# PrimeTime.net
KiCad netlist of a schematic drawn in EAGLE
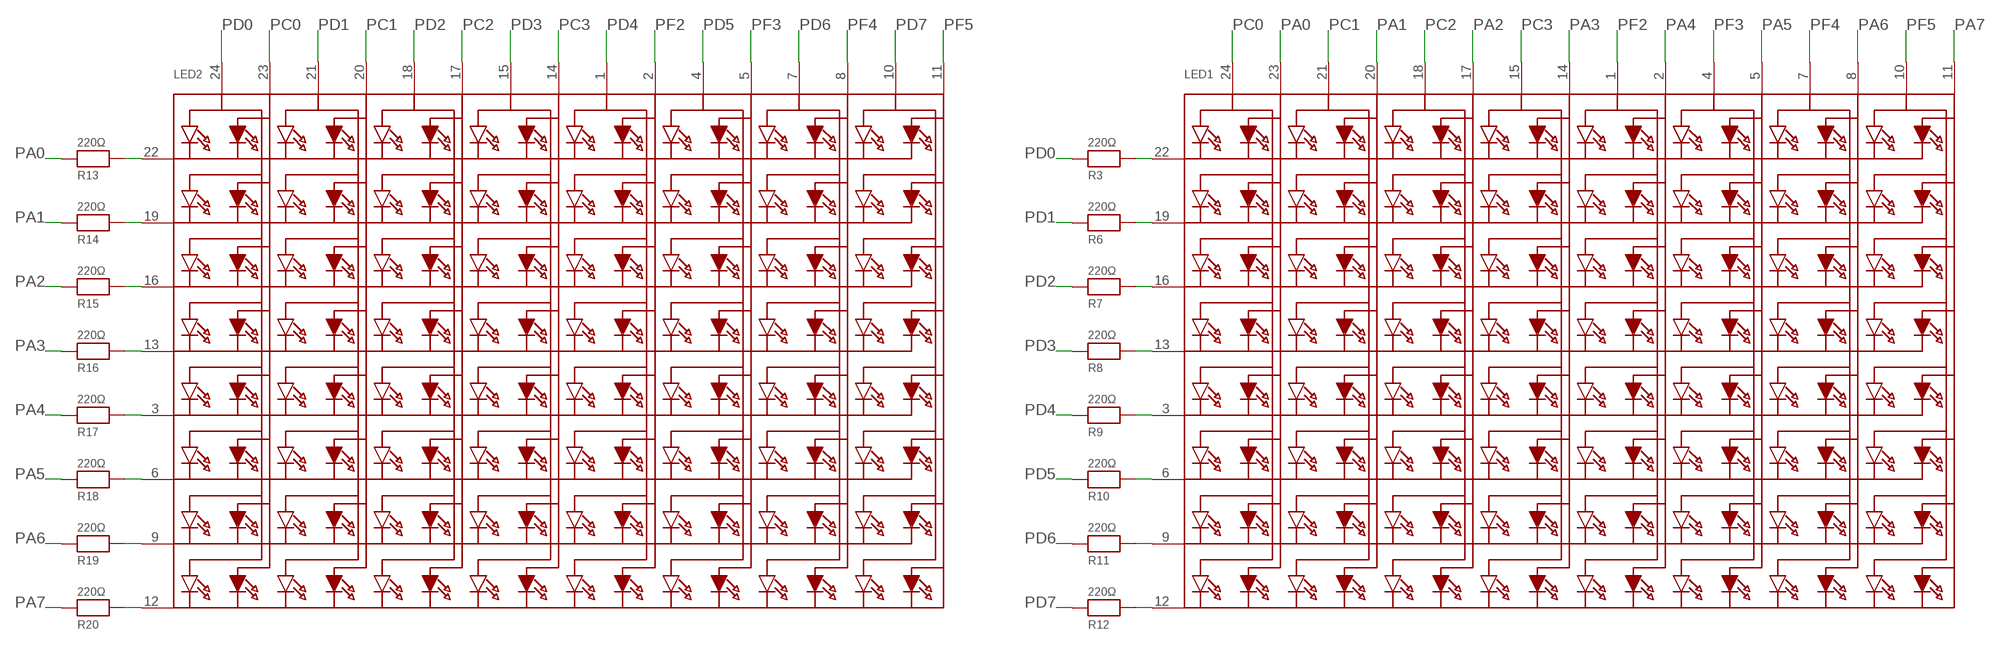
[diagram p0: schematic, sheet 1, part 1 of 2]
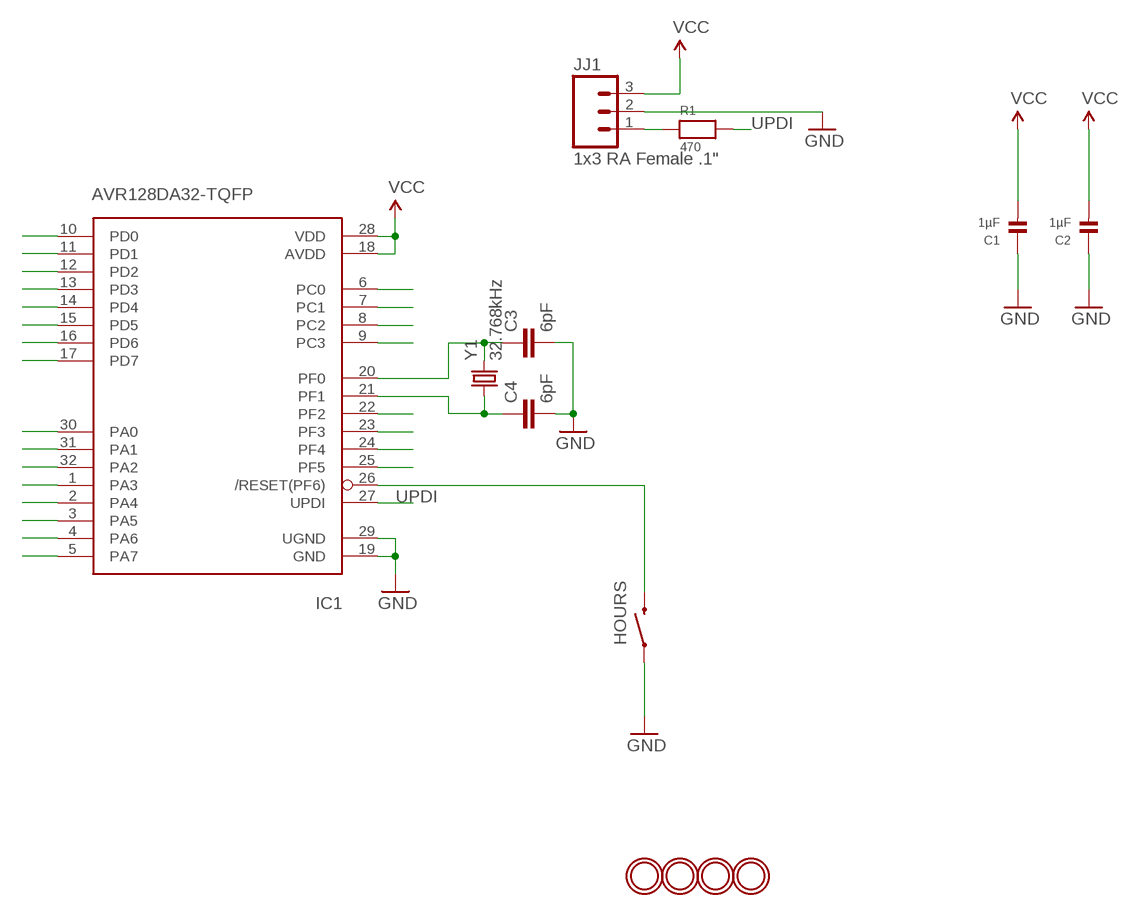
[diagram p1: schematic, sheet 1, part 2 of 2]

(export (version "E")
  (design (tool "Eeschema 10.0.6"))
  (components
    (comp (ref "C1")
      (value "1µF")
      (footprint "eagle-import:_0805MP")
      (libsource (lib "eagle-import") (part "CAP_CERAMIC_0805MP"))
    )
    (comp (ref "C2")
      (value "1µF")
      (footprint "eagle-import:_0805MP")
      (libsource (lib "eagle-import") (part "CAP_CERAMIC_0805MP"))
    )
    (comp (ref "C3")
      (value "6pF")
      (footprint "eagle-import:0805")
      (libsource (lib "eagle-import") (part "CAP0805"))
    )
    (comp (ref "C4")
      (value "6pF")
      (footprint "eagle-import:0805")
      (libsource (lib "eagle-import") (part "CAP0805"))
    )
    (comp (ref "HOURS")
      (value "SWITCH-MOMENTARY-2SMD-4")
      (footprint "eagle-import:TACTILE_SWITCH_TALL")
      (libsource (lib "eagle-import") (part "SWITCH-MOMENTARY-2SMD-4"))
    )
    (comp (ref "IC1")
      (value "AVR128DA32-TQFP")
      (footprint "eagle-import:TQFP32-08")
      (libsource (lib "eagle-import") (part "AVR128DA32-TQFP"))
    )
    (comp (ref "JJ1")
      (value "1x3 RA Female .1\"")
      (footprint "eagle-import:1X03_SMD_RA_FEMALE")
      (libsource (lib "eagle-import") (part "M03SMD_RA_FEMALE"))
    )
    (comp (ref "LED1")
      (value "SEGMENT_8X8_BICOLOR_ROWCATHODEMI2A883XX")
      (footprint "eagle-import:SEGMENT_BICOL_BL-M12A883XX")
      (libsource (lib "eagle-import") (part "SEGMENT_8X8_BICOLOR_ROWCATHODEMI2A883XX"))
    )
    (comp (ref "LED2")
      (value "SEGMENT_8X8_BICOLOR_ROWCATHODEMI2A883XX")
      (footprint "eagle-import:SEGMENT_BICOL_BL-M12A883XX")
      (libsource (lib "eagle-import") (part "SEGMENT_8X8_BICOLOR_ROWCATHODEMI2A883XX"))
    )
    (comp (ref "R1")
      (value "470")
      (footprint "eagle-import:_0805MP")
      (libsource (lib "eagle-import") (part "RESISTOR_0805MP"))
    )
    (comp (ref "R3")
      (value "220Ω")
      (footprint "eagle-import:_0805MP")
      (libsource (lib "eagle-import") (part "RESISTOR_0805MP"))
    )
    (comp (ref "R6")
      (value "220Ω")
      (footprint "eagle-import:_0805MP")
      (libsource (lib "eagle-import") (part "RESISTOR_0805MP"))
    )
    (comp (ref "R7")
      (value "220Ω")
      (footprint "eagle-import:_0805MP")
      (libsource (lib "eagle-import") (part "RESISTOR_0805MP"))
    )
    (comp (ref "R8")
      (value "220Ω")
      (footprint "eagle-import:_0805MP")
      (libsource (lib "eagle-import") (part "RESISTOR_0805MP"))
    )
    (comp (ref "R9")
      (value "220Ω")
      (footprint "eagle-import:_0805MP")
      (libsource (lib "eagle-import") (part "RESISTOR_0805MP"))
    )
    (comp (ref "R10")
      (value "220Ω")
      (footprint "eagle-import:_0805MP")
      (libsource (lib "eagle-import") (part "RESISTOR_0805MP"))
    )
    (comp (ref "R11")
      (value "220Ω")
      (footprint "eagle-import:_0805MP")
      (libsource (lib "eagle-import") (part "RESISTOR_0805MP"))
    )
    (comp (ref "R12")
      (value "220Ω")
      (footprint "eagle-import:_0805MP")
      (libsource (lib "eagle-import") (part "RESISTOR_0805MP"))
    )
    (comp (ref "R13")
      (value "220Ω")
      (footprint "eagle-import:_0805MP")
      (libsource (lib "eagle-import") (part "RESISTOR_0805MP"))
    )
    (comp (ref "R14")
      (value "220Ω")
      (footprint "eagle-import:_0805MP")
      (libsource (lib "eagle-import") (part "RESISTOR_0805MP"))
    )
    (comp (ref "R15")
      (value "220Ω")
      (footprint "eagle-import:_0805MP")
      (libsource (lib "eagle-import") (part "RESISTOR_0805MP"))
    )
    (comp (ref "R16")
      (value "220Ω")
      (footprint "eagle-import:_0805MP")
      (libsource (lib "eagle-import") (part "RESISTOR_0805MP"))
    )
    (comp (ref "R17")
      (value "220Ω")
      (footprint "eagle-import:_0805MP")
      (libsource (lib "eagle-import") (part "RESISTOR_0805MP"))
    )
    (comp (ref "R18")
      (value "220Ω")
      (footprint "eagle-import:_0805MP")
      (libsource (lib "eagle-import") (part "RESISTOR_0805MP"))
    )
    (comp (ref "R19")
      (value "220Ω")
      (footprint "eagle-import:_0805MP")
      (libsource (lib "eagle-import") (part "RESISTOR_0805MP"))
    )
    (comp (ref "R20")
      (value "220Ω")
      (footprint "eagle-import:_0805MP")
      (libsource (lib "eagle-import") (part "RESISTOR_0805MP"))
    )
    (comp (ref "U$1")
      (value "MOUNTINGHOLE2.5")
      (footprint "eagle-import:MOUNTINGHOLE_2.5_PLATED")
      (libsource (lib "eagle-import") (part "MOUNTINGHOLE2.5"))
    )
    (comp (ref "U$4")
      (value "MOUNTINGHOLE2.5")
      (footprint "eagle-import:MOUNTINGHOLE_2.5_PLATED")
      (libsource (lib "eagle-import") (part "MOUNTINGHOLE2.5"))
    )
    (comp (ref "U$5")
      (value "MOUNTINGHOLE2.5")
      (footprint "eagle-import:MOUNTINGHOLE_2.5_PLATED")
      (libsource (lib "eagle-import") (part "MOUNTINGHOLE2.5"))
    )
    (comp (ref "U$9")
      (value "MOUNTINGHOLE2.5")
      (footprint "eagle-import:MOUNTINGHOLE_2.5_PLATED")
      (libsource (lib "eagle-import") (part "MOUNTINGHOLE2.5"))
    )
    (comp (ref "Y1")
      (value "32.768kHz")
      (footprint "eagle-import:CRYSTAL-SMD-3.2X1.5MM")
      (libsource (lib "eagle-import") (part "CRYSTAL3.2X1.5MM"))
    )
  )
  (nets
    (net (code "1") (name "/PA0") (class "Default")
      (node (ref "IC1") (pin "30") (pinfunction "PA0_30") (pintype "bidirectional"))
      (node (ref "LED1") (pin "23") (pinfunction "A2_23") (pintype "bidirectional"))
      (node (ref "R13") (pin "1") (pinfunction "1_1") (pintype "passive"))
    )
    (net (code "2") (name "/PA1") (class "Default")
      (node (ref "IC1") (pin "31") (pinfunction "PA1_31") (pintype "bidirectional"))
      (node (ref "LED1") (pin "20") (pinfunction "A4_20") (pintype "bidirectional"))
      (node (ref "R14") (pin "1") (pinfunction "1_1") (pintype "passive"))
    )
    (net (code "3") (name "/PA2") (class "Default")
      (node (ref "IC1") (pin "32") (pinfunction "PA2_32") (pintype "bidirectional"))
      (node (ref "LED1") (pin "17") (pinfunction "A6_17") (pintype "bidirectional"))
      (node (ref "R15") (pin "1") (pinfunction "1_1") (pintype "passive"))
    )
    (net (code "4") (name "/PA3") (class "Default")
      (node (ref "IC1") (pin "1") (pinfunction "PA3_1") (pintype "bidirectional"))
      (node (ref "LED1") (pin "14") (pinfunction "A8_14") (pintype "bidirectional"))
      (node (ref "R16") (pin "1") (pinfunction "1_1") (pintype "passive"))
    )
    (net (code "5") (name "/PA4") (class "Default")
      (node (ref "IC1") (pin "2") (pinfunction "PA4_2") (pintype "bidirectional"))
      (node (ref "LED1") (pin "2") (pinfunction "A10_2") (pintype "bidirectional"))
      (node (ref "R17") (pin "1") (pinfunction "1_1") (pintype "passive"))
    )
    (net (code "6") (name "/PA5") (class "Default")
      (node (ref "IC1") (pin "3") (pinfunction "PA5_3") (pintype "bidirectional"))
      (node (ref "LED1") (pin "5") (pinfunction "A12_5") (pintype "bidirectional"))
      (node (ref "R18") (pin "1") (pinfunction "1_1") (pintype "passive"))
    )
    (net (code "7") (name "/PA6") (class "Default")
      (node (ref "IC1") (pin "4") (pinfunction "PA6_4") (pintype "bidirectional"))
      (node (ref "LED1") (pin "8") (pinfunction "A14_8") (pintype "bidirectional"))
      (node (ref "R19") (pin "1") (pinfunction "1_1") (pintype "passive"))
    )
    (net (code "8") (name "/PA7") (class "Default")
      (node (ref "IC1") (pin "5") (pinfunction "PA7_5") (pintype "bidirectional"))
      (node (ref "LED1") (pin "11") (pinfunction "A16_11") (pintype "bidirectional"))
      (node (ref "R20") (pin "1") (pinfunction "1_1") (pintype "passive"))
    )
    (net (code "9") (name "/PC0") (class "Default")
      (node (ref "IC1") (pin "6") (pinfunction "PC0_6") (pintype "bidirectional"))
      (node (ref "LED1") (pin "24") (pinfunction "A1_24") (pintype "bidirectional"))
      (node (ref "LED2") (pin "23") (pinfunction "A2_23") (pintype "bidirectional"))
    )
    (net (code "10") (name "/PC1") (class "Default")
      (node (ref "IC1") (pin "7") (pinfunction "PC1_7") (pintype "bidirectional"))
      (node (ref "LED1") (pin "21") (pinfunction "A3_21") (pintype "bidirectional"))
      (node (ref "LED2") (pin "20") (pinfunction "A4_20") (pintype "bidirectional"))
    )
    (net (code "11") (name "/PC2") (class "Default")
      (node (ref "IC1") (pin "8") (pinfunction "PC2_8") (pintype "bidirectional"))
      (node (ref "LED1") (pin "18") (pinfunction "A5_18") (pintype "bidirectional"))
      (node (ref "LED2") (pin "17") (pinfunction "A6_17") (pintype "bidirectional"))
    )
    (net (code "12") (name "/PC3") (class "Default")
      (node (ref "IC1") (pin "9") (pinfunction "PC3_9") (pintype "bidirectional"))
      (node (ref "LED1") (pin "15") (pinfunction "A7_15") (pintype "bidirectional"))
      (node (ref "LED2") (pin "14") (pinfunction "A8_14") (pintype "bidirectional"))
    )
    (net (code "13") (name "/PD0") (class "Default")
      (node (ref "IC1") (pin "10") (pinfunction "PD0_10") (pintype "bidirectional"))
      (node (ref "LED2") (pin "24") (pinfunction "A1_24") (pintype "bidirectional"))
      (node (ref "R3") (pin "1") (pinfunction "1_1") (pintype "passive"))
    )
    (net (code "14") (name "/PD1") (class "Default")
      (node (ref "IC1") (pin "11") (pinfunction "PD1_11") (pintype "bidirectional"))
      (node (ref "LED2") (pin "21") (pinfunction "A3_21") (pintype "bidirectional"))
      (node (ref "R6") (pin "1") (pinfunction "1_1") (pintype "passive"))
    )
    (net (code "15") (name "/PD2") (class "Default")
      (node (ref "IC1") (pin "12") (pinfunction "PD2_12") (pintype "bidirectional"))
      (node (ref "LED2") (pin "18") (pinfunction "A5_18") (pintype "bidirectional"))
      (node (ref "R7") (pin "1") (pinfunction "1_1") (pintype "passive"))
    )
    (net (code "16") (name "/PD3") (class "Default")
      (node (ref "IC1") (pin "13") (pinfunction "PD3_13") (pintype "bidirectional"))
      (node (ref "LED2") (pin "15") (pinfunction "A7_15") (pintype "bidirectional"))
      (node (ref "R8") (pin "1") (pinfunction "1_1") (pintype "passive"))
    )
    (net (code "17") (name "/PD4") (class "Default")
      (node (ref "IC1") (pin "14") (pinfunction "PD4_14") (pintype "bidirectional"))
      (node (ref "LED2") (pin "1") (pinfunction "A9_1") (pintype "bidirectional"))
      (node (ref "R9") (pin "1") (pinfunction "1_1") (pintype "passive"))
    )
    (net (code "18") (name "/PD5") (class "Default")
      (node (ref "IC1") (pin "15") (pinfunction "PD5_15") (pintype "bidirectional"))
      (node (ref "LED2") (pin "4") (pinfunction "A11_4") (pintype "bidirectional"))
      (node (ref "R10") (pin "1") (pinfunction "1_1") (pintype "passive"))
    )
    (net (code "19") (name "/PD6") (class "Default")
      (node (ref "IC1") (pin "16") (pinfunction "PD6_16") (pintype "bidirectional"))
      (node (ref "LED2") (pin "7") (pinfunction "A13_7") (pintype "bidirectional"))
      (node (ref "R11") (pin "1") (pinfunction "1_1") (pintype "passive"))
    )
    (net (code "20") (name "/PD7") (class "Default")
      (node (ref "IC1") (pin "17") (pinfunction "PD7_17") (pintype "bidirectional"))
      (node (ref "LED2") (pin "10") (pinfunction "A15_10") (pintype "bidirectional"))
      (node (ref "R12") (pin "1") (pinfunction "1_1") (pintype "passive"))
    )
    (net (code "21") (name "/PF2") (class "Default")
      (node (ref "IC1") (pin "22") (pinfunction "PF2_22") (pintype "bidirectional"))
      (node (ref "LED1") (pin "1") (pinfunction "A9_1") (pintype "bidirectional"))
      (node (ref "LED2") (pin "2") (pinfunction "A10_2") (pintype "bidirectional"))
    )
    (net (code "22") (name "/PF3") (class "Default")
      (node (ref "IC1") (pin "23") (pinfunction "PF3_23") (pintype "bidirectional"))
      (node (ref "LED1") (pin "4") (pinfunction "A11_4") (pintype "bidirectional"))
      (node (ref "LED2") (pin "5") (pinfunction "A12_5") (pintype "bidirectional"))
    )
    (net (code "23") (name "/PF4") (class "Default")
      (node (ref "IC1") (pin "24") (pinfunction "PF4_24") (pintype "bidirectional"))
      (node (ref "LED1") (pin "7") (pinfunction "A13_7") (pintype "bidirectional"))
      (node (ref "LED2") (pin "8") (pinfunction "A14_8") (pintype "bidirectional"))
    )
    (net (code "24") (name "/PF5") (class "Default")
      (node (ref "IC1") (pin "25") (pinfunction "PF5_25") (pintype "bidirectional"))
      (node (ref "LED1") (pin "10") (pinfunction "A15_10") (pintype "bidirectional"))
      (node (ref "LED2") (pin "11") (pinfunction "A16_11") (pintype "bidirectional"))
    )
    (net (code "25") (name "/UPDI") (class "Default")
      (node (ref "IC1") (pin "27") (pinfunction "UPDI_27") (pintype "bidirectional"))
      (node (ref "R1") (pin "2") (pinfunction "2_2") (pintype "passive"))
    )
    (net (code "26") (name "GND") (class "Default")
      (node (ref "C1") (pin "1") (pinfunction "P$1_1") (pintype "passive"))
      (node (ref "C2") (pin "1") (pinfunction "P$1_1") (pintype "passive"))
      (node (ref "C3") (pin "2") (pinfunction "2_2") (pintype "passive"))
      (node (ref "C4") (pin "2") (pinfunction "2_2") (pintype "passive"))
      (node (ref "HOURS") (pin "A2") (pinfunction "1_A2") (pintype "passive"))
      (node (ref "IC1") (pin "19") (pinfunction "GND_19") (pintype "bidirectional"))
      (node (ref "IC1") (pin "29") (pinfunction "UGND_29") (pintype "bidirectional"))
      (node (ref "JJ1") (pin "2") (pinfunction "2_2") (pintype "passive"))
    )
    (net (code "27") (name "Net-(HOURS-2)") (class "Default")
      (node (ref "HOURS") (pin "B2") (pinfunction "2_B2") (pintype "passive"))
      (node (ref "IC1") (pin "26") (pinfunction "/RESET(PF6)_26") (pintype "bidirectional"))
    )
    (net (code "28") (name "Net-(IC1-PF0)") (class "Default")
      (node (ref "C3") (pin "1") (pinfunction "1_1") (pintype "passive"))
      (node (ref "IC1") (pin "20") (pinfunction "PF0_20") (pintype "bidirectional"))
      (node (ref "Y1") (pin "P$2") (pinfunction "2_P$2") (pintype "passive"))
    )
    (net (code "29") (name "Net-(IC1-PF1)") (class "Default")
      (node (ref "C4") (pin "1") (pinfunction "1_1") (pintype "passive"))
      (node (ref "IC1") (pin "21") (pinfunction "PF1_21") (pintype "bidirectional"))
      (node (ref "Y1") (pin "P$1") (pinfunction "1_P$1") (pintype "passive"))
    )
    (net (code "30") (name "Net-(JJ1-Pad1)") (class "Default")
      (node (ref "JJ1") (pin "1") (pinfunction "1_1") (pintype "passive"))
      (node (ref "R1") (pin "1") (pinfunction "1_1") (pintype "passive"))
    )
    (net (code "31") (name "Net-(LED1-K1)") (class "Default")
      (node (ref "LED1") (pin "22") (pinfunction "K1_22") (pintype "bidirectional"))
      (node (ref "R3") (pin "2") (pinfunction "2_2") (pintype "passive"))
    )
    (net (code "32") (name "Net-(LED1-K2)") (class "Default")
      (node (ref "LED1") (pin "19") (pinfunction "K2_19") (pintype "bidirectional"))
      (node (ref "R6") (pin "2") (pinfunction "2_2") (pintype "passive"))
    )
    (net (code "33") (name "Net-(LED1-K3)") (class "Default")
      (node (ref "LED1") (pin "16") (pinfunction "K3_16") (pintype "bidirectional"))
      (node (ref "R7") (pin "2") (pinfunction "2_2") (pintype "passive"))
    )
    (net (code "34") (name "Net-(LED1-K4)") (class "Default")
      (node (ref "LED1") (pin "13") (pinfunction "K4_13") (pintype "bidirectional"))
      (node (ref "R8") (pin "2") (pinfunction "2_2") (pintype "passive"))
    )
    (net (code "35") (name "Net-(LED1-K5)") (class "Default")
      (node (ref "LED1") (pin "3") (pinfunction "K5_3") (pintype "bidirectional"))
      (node (ref "R9") (pin "2") (pinfunction "2_2") (pintype "passive"))
    )
    (net (code "36") (name "Net-(LED1-K6)") (class "Default")
      (node (ref "LED1") (pin "6") (pinfunction "K6_6") (pintype "bidirectional"))
      (node (ref "R10") (pin "2") (pinfunction "2_2") (pintype "passive"))
    )
    (net (code "37") (name "Net-(LED1-K7)") (class "Default")
      (node (ref "LED1") (pin "9") (pinfunction "K7_9") (pintype "bidirectional"))
      (node (ref "R11") (pin "2") (pinfunction "2_2") (pintype "passive"))
    )
    (net (code "38") (name "Net-(LED1-K8)") (class "Default")
      (node (ref "LED1") (pin "12") (pinfunction "K8_12") (pintype "bidirectional"))
      (node (ref "R12") (pin "2") (pinfunction "2_2") (pintype "passive"))
    )
    (net (code "39") (name "Net-(LED2-K1)") (class "Default")
      (node (ref "LED2") (pin "22") (pinfunction "K1_22") (pintype "bidirectional"))
      (node (ref "R13") (pin "2") (pinfunction "2_2") (pintype "passive"))
    )
    (net (code "40") (name "Net-(LED2-K2)") (class "Default")
      (node (ref "LED2") (pin "19") (pinfunction "K2_19") (pintype "bidirectional"))
      (node (ref "R14") (pin "2") (pinfunction "2_2") (pintype "passive"))
    )
    (net (code "41") (name "Net-(LED2-K3)") (class "Default")
      (node (ref "LED2") (pin "16") (pinfunction "K3_16") (pintype "bidirectional"))
      (node (ref "R15") (pin "2") (pinfunction "2_2") (pintype "passive"))
    )
    (net (code "42") (name "Net-(LED2-K4)") (class "Default")
      (node (ref "LED2") (pin "13") (pinfunction "K4_13") (pintype "bidirectional"))
      (node (ref "R16") (pin "2") (pinfunction "2_2") (pintype "passive"))
    )
    (net (code "43") (name "Net-(LED2-K5)") (class "Default")
      (node (ref "LED2") (pin "3") (pinfunction "K5_3") (pintype "bidirectional"))
      (node (ref "R17") (pin "2") (pinfunction "2_2") (pintype "passive"))
    )
    (net (code "44") (name "Net-(LED2-K6)") (class "Default")
      (node (ref "LED2") (pin "6") (pinfunction "K6_6") (pintype "bidirectional"))
      (node (ref "R18") (pin "2") (pinfunction "2_2") (pintype "passive"))
    )
    (net (code "45") (name "Net-(LED2-K7)") (class "Default")
      (node (ref "LED2") (pin "9") (pinfunction "K7_9") (pintype "bidirectional"))
      (node (ref "R19") (pin "2") (pinfunction "2_2") (pintype "passive"))
    )
    (net (code "46") (name "Net-(LED2-K8)") (class "Default")
      (node (ref "LED2") (pin "12") (pinfunction "K8_12") (pintype "bidirectional"))
      (node (ref "R20") (pin "2") (pinfunction "2_2") (pintype "passive"))
    )
    (net (code "47") (name "VCC") (class "Default")
      (node (ref "C1") (pin "2") (pinfunction "P$2_2") (pintype "passive"))
      (node (ref "C2") (pin "2") (pinfunction "P$2_2") (pintype "passive"))
      (node (ref "IC1") (pin "18") (pinfunction "AVDD_18") (pintype "bidirectional"))
      (node (ref "IC1") (pin "28") (pinfunction "VDD_28") (pintype "bidirectional"))
      (node (ref "JJ1") (pin "3") (pinfunction "3_3") (pintype "passive"))
    )
  )
)
